# Communication.net
KiCad netlist of a schematic drawn in Altium Designer
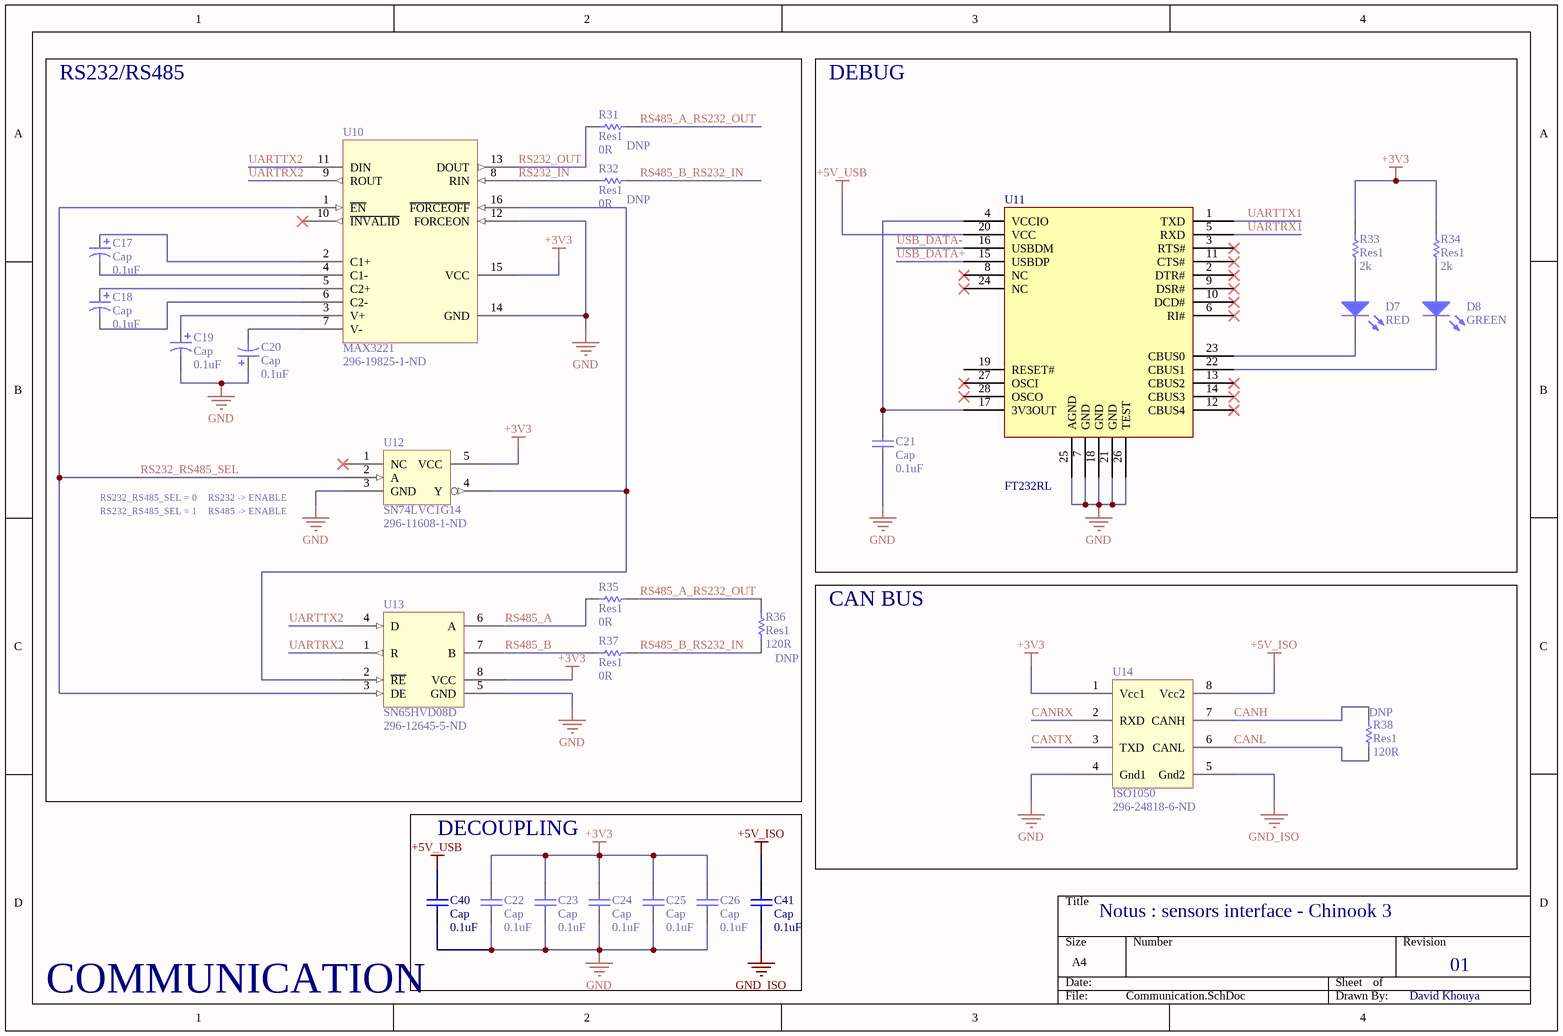
[diagram p0: Communication.SchDoc]

(export (version "E")
  (design (tool "Eeschema 10.0.6"))
  (components
    (comp (ref "C17")
      (value "Cap")
      (footprint "C0805")
      (description "Polarized Capacitor (Surface Mount)")
      (fields (field (name "ALTIUM_VALUE") "0.1uF") (field (name "PUBLISHER") "Altium Limited"))
      (libsource (lib "Miscellaneous Devices") (part "Cap Pol3"))
    )
    (comp (ref "C18")
      (value "Cap")
      (footprint "C0805")
      (description "Polarized Capacitor (Surface Mount)")
      (fields (field (name "ALTIUM_VALUE") "0.1uF") (field (name "PUBLISHER") "Altium Limited"))
      (libsource (lib "Miscellaneous Devices") (part "Cap Pol3"))
    )
    (comp (ref "C19")
      (value "Cap")
      (footprint "C0805")
      (description "Polarized Capacitor (Surface Mount)")
      (fields (field (name "ALTIUM_VALUE") "0.1uF") (field (name "PUBLISHER") "Altium Limited"))
      (libsource (lib "Miscellaneous Devices") (part "Cap Pol3"))
    )
    (comp (ref "C20")
      (value "Cap")
      (footprint "C0805")
      (description "Polarized Capacitor (Surface Mount)")
      (fields (field (name "ALTIUM_VALUE") "0.1uF") (field (name "PUBLISHER") "Altium Limited"))
      (libsource (lib "Miscellaneous Devices") (part "Cap Pol3"))
    )
    (comp (ref "C21")
      (value "Cap")
      (footprint "RESC2012N")
      (description "Capacitor")
      (fields (field (name "ALTIUM_VALUE") "0.1uF") (field (name "PUBLISHER") "Altium Limited"))
      (libsource (lib "Miscellaneous Devices") (part "Cap"))
    )
    (comp (ref "C22")
      (value "Cap")
      (footprint "RESC2012N")
      (description "Capacitor")
      (fields (field (name "ALTIUM_VALUE") "0.1uF") (field (name "PUBLISHER") "Altium Limited"))
      (libsource (lib "Miscellaneous Devices") (part "Cap"))
    )
    (comp (ref "C23")
      (value "Cap")
      (footprint "RESC2012N")
      (description "Capacitor")
      (fields (field (name "ALTIUM_VALUE") "0.1uF") (field (name "PUBLISHER") "Altium Limited"))
      (libsource (lib "Miscellaneous Devices") (part "Cap"))
    )
    (comp (ref "C24")
      (value "Cap")
      (footprint "RESC2012N")
      (description "Capacitor")
      (fields (field (name "ALTIUM_VALUE") "0.1uF") (field (name "PUBLISHER") "Altium Limited"))
      (libsource (lib "Miscellaneous Devices") (part "Cap"))
    )
    (comp (ref "C25")
      (value "Cap")
      (footprint "RESC2012N")
      (description "Capacitor")
      (fields (field (name "ALTIUM_VALUE") "0.1uF") (field (name "PUBLISHER") "Altium Limited"))
      (libsource (lib "Miscellaneous Devices") (part "Cap"))
    )
    (comp (ref "C26")
      (value "Cap")
      (footprint "RESC2012N")
      (description "Capacitor")
      (fields (field (name "ALTIUM_VALUE") "0.1uF") (field (name "PUBLISHER") "Altium Limited"))
      (libsource (lib "Miscellaneous Devices") (part "Cap"))
    )
    (comp (ref "C40")
      (value "Cap")
      (footprint "RESC2012N")
      (description "Capacitor")
      (fields (field (name "ALTIUM_VALUE") "0.1uF") (field (name "PUBLISHER") "Altium Limited"))
      (libsource (lib "Miscellaneous Devices") (part "Cap"))
    )
    (comp (ref "C41")
      (value "Cap")
      (footprint "RESC2012N")
      (description "Capacitor")
      (fields (field (name "ALTIUM_VALUE") "0.1uF") (field (name "PUBLISHER") "Altium Limited"))
      (libsource (lib "Miscellaneous Devices") (part "Cap"))
    )
    (comp (ref "D7")
      (value "RED")
      (footprint "0805_Diode")
      (description "Typical INFRARED GaAs LED")
      (fields (field (name "PUBLISHER") "Altium Limited"))
      (libsource (lib "Miscellaneous Devices") (part "LED0"))
    )
    (comp (ref "D8")
      (value "GREEN")
      (footprint "0805_Diode")
      (description "Typical INFRARED GaAs LED")
      (fields (field (name "PUBLISHER") "Altium Limited"))
      (libsource (lib "Miscellaneous Devices") (part "LED0"))
    )
    (comp (ref "R31")
      (value "Res1")
      (footprint "RESC2012N")
      (description "Resistor")
      (fields
        (field (name "ALTIUM_VALUE") "0R")
        (field (name "DNP") "DNP")
        (field (name "PUBLISHER") "Altium Limited")
      )
      (libsource (lib "Miscellaneous Devices") (part "Res1"))
    )
    (comp (ref "R32")
      (value "Res1")
      (footprint "RESC2012N")
      (description "Resistor")
      (fields
        (field (name "ALTIUM_VALUE") "0R")
        (field (name "DNP") "DNP")
        (field (name "PUBLISHER") "Altium Limited")
      )
      (libsource (lib "Miscellaneous Devices") (part "Res1"))
    )
    (comp (ref "R33")
      (value "Res1")
      (footprint "RESC2012N")
      (description "Resistor")
      (fields (field (name "ALTIUM_VALUE") "2k") (field (name "PUBLISHER") "Altium Limited"))
      (libsource (lib "Miscellaneous Devices") (part "Res1"))
    )
    (comp (ref "R34")
      (value "Res1")
      (footprint "RESC2012N")
      (description "Resistor")
      (fields (field (name "ALTIUM_VALUE") "2k") (field (name "PUBLISHER") "Altium Limited"))
      (libsource (lib "Miscellaneous Devices") (part "Res1"))
    )
    (comp (ref "R35")
      (value "Res1")
      (footprint "RESC2012N")
      (description "Resistor")
      (fields (field (name "ALTIUM_VALUE") "0R") (field (name "PUBLISHER") "Altium Limited"))
      (libsource (lib "Miscellaneous Devices") (part "Res1"))
    )
    (comp (ref "R36")
      (value "Res1")
      (footprint "RESC2012N")
      (description "Resistor")
      (fields
        (field (name "ALTIUM_VALUE") "120R")
        (field (name "DNP") "DNP")
        (field (name "PUBLISHER") "Altium Limited")
      )
      (libsource (lib "Miscellaneous Devices") (part "Res1"))
    )
    (comp (ref "R37")
      (value "Res1")
      (footprint "RESC2012N")
      (description "Resistor")
      (fields (field (name "ALTIUM_VALUE") "0R") (field (name "PUBLISHER") "Altium Limited"))
      (libsource (lib "Miscellaneous Devices") (part "Res1"))
    )
    (comp (ref "R38")
      (value "Res1")
      (footprint "RESC2012N")
      (description "Resistor")
      (fields
        (field (name "ALTIUM_VALUE") "120R")
        (field (name "DNP") "DNP")
        (field (name "PUBLISHER") "Altium Limited")
      )
      (libsource (lib "Miscellaneous Devices") (part "Res1"))
    )
    (comp (ref "U10")
      (value "MAX3221")
      (footprint "SSOP16_M")
      (description "RS232 to TTL")
      (fields (field (name "SUPPLIER PART NUMBER 1") "296-19825-1-ND"))
      (libsource (lib "dkhouya") (part "MAX3221"))
    )
    (comp (ref "U11")
      (value "FT232RL")
      (footprint "ssop-28")
      (description "USB UART IC")
      (libsource (lib "dkhouya") (part "FT232RL"))
    )
    (comp (ref "U12")
      (value "SN74LVC1G14")
      (footprint "SOT23-5AM")
      (description "Inverter Gate")
      (fields (field (name "SUPPLIER PART NUMBER 1") "296-11608-1-ND"))
      (libsource (lib "dkhouya") (part "SN74LVC1G14"))
    )
    (comp (ref "U13")
      (value "SN65HVD08D")
      (footprint "8SOIC-2")
      (description "RS485 to TTL")
      (fields (field (name "SUPPLIER PART NUMBER 1") "296-12645-5-ND"))
      (libsource (lib "dkhouya") (part "SN65HVD08D"))
    )
    (comp (ref "U14")
      (value "ISO1050")
      (footprint "SOP-8")
      (description "ISOLATED CAN TRANSCEIVER")
      (fields (field (name "SUPPLIER PART NUMBER 1") "296-24818-6-ND"))
      (libsource (lib "dkhouya") (part "ISO1050"))
    )
  )
  (nets
    (net (code "1") (name "+3V3") (class "Default")
      (node (ref "C22") (pin "2") (pinfunction "2_2") (pintype "passive"))
      (node (ref "C23") (pin "2") (pinfunction "2_2") (pintype "passive"))
      (node (ref "C24") (pin "2") (pinfunction "2_2") (pintype "passive"))
      (node (ref "C25") (pin "2") (pinfunction "2_2") (pintype "passive"))
      (node (ref "C26") (pin "2") (pinfunction "2_2") (pintype "passive"))
      (node (ref "R33") (pin "1") (pinfunction "1_1") (pintype "passive"))
      (node (ref "R34") (pin "1") (pinfunction "1_1") (pintype "passive"))
      (node (ref "U10") (pin "15") (pinfunction "VCC_15") (pintype "power_in"))
      (node (ref "U12") (pin "5") (pinfunction "VCC_5") (pintype "power_in"))
      (node (ref "U13") (pin "8") (pinfunction "VCC_8") (pintype "power_in"))
      (node (ref "U14") (pin "1") (pinfunction "Vcc1_1") (pintype "power_in"))
    )
    (net (code "2") (name "+5V_ISO") (class "Default")
      (node (ref "C41") (pin "2") (pinfunction "2_2") (pintype "passive"))
      (node (ref "U14") (pin "8") (pinfunction "Vcc2_8") (pintype "passive"))
    )
    (net (code "3") (name "+5V_USB") (class "Default")
      (node (ref "C40") (pin "2") (pinfunction "2_2") (pintype "passive"))
      (node (ref "U11") (pin "20") (pinfunction "VCC_20") (pintype "passive"))
    )
    (net (code "4") (name "/CANH") (class "Default")
      (node (ref "R38") (pin "1") (pinfunction "1_1") (pintype "passive"))
      (node (ref "U14") (pin "7") (pinfunction "CANH_7") (pintype "passive"))
    )
    (net (code "5") (name "/CANL") (class "Default")
      (node (ref "R38") (pin "2") (pinfunction "2_2") (pintype "passive"))
      (node (ref "U14") (pin "6") (pinfunction "CANL_6") (pintype "passive"))
    )
    (net (code "6") (name "/CANRX") (class "Default")
      (node (ref "U14") (pin "2") (pinfunction "RXD_2") (pintype "passive"))
    )
    (net (code "7") (name "/CANTX") (class "Default")
      (node (ref "U14") (pin "3") (pinfunction "TXD_3") (pintype "passive"))
    )
    (net (code "8") (name "/RS232_IN") (class "Default")
      (node (ref "R32") (pin "1") (pinfunction "1_1") (pintype "passive"))
      (node (ref "U10") (pin "8") (pinfunction "RIN_8") (pintype "input"))
    )
    (net (code "9") (name "/RS232_OUT") (class "Default")
      (node (ref "R31") (pin "1") (pinfunction "1_1") (pintype "passive"))
      (node (ref "U10") (pin "13") (pinfunction "DOUT_13") (pintype "output"))
    )
    (net (code "10") (name "/RS232_RS485_SEL") (class "Default")
      (node (ref "U10") (pin "1") (pinfunction "~{EN}_1") (pintype "input"))
      (node (ref "U12") (pin "2") (pinfunction "A_2") (pintype "input"))
      (node (ref "U13") (pin "3") (pinfunction "DE_3") (pintype "input"))
    )
    (net (code "11") (name "/RS485_A") (class "Default")
      (node (ref "R35") (pin "1") (pinfunction "1_1") (pintype "passive"))
      (node (ref "U13") (pin "6") (pinfunction "A_6") (pintype "passive"))
    )
    (net (code "12") (name "/RS485_A_RS232_OUT") (class "Default")
      (node (ref "R31") (pin "2") (pinfunction "2_2") (pintype "passive"))
      (node (ref "R35") (pin "2") (pinfunction "2_2") (pintype "passive"))
      (node (ref "R36") (pin "2") (pinfunction "2_2") (pintype "passive"))
    )
    (net (code "13") (name "/RS485_B") (class "Default")
      (node (ref "R37") (pin "1") (pinfunction "1_1") (pintype "passive"))
      (node (ref "U13") (pin "7") (pinfunction "B_7") (pintype "passive"))
    )
    (net (code "14") (name "/RS485_B_RS232_IN") (class "Default")
      (node (ref "R32") (pin "2") (pinfunction "2_2") (pintype "passive"))
      (node (ref "R36") (pin "1") (pinfunction "1_1") (pintype "passive"))
      (node (ref "R37") (pin "2") (pinfunction "2_2") (pintype "passive"))
    )
    (net (code "15") (name "/UARTRX1") (class "Default")
      (node (ref "U11") (pin "5") (pinfunction "RXD_5") (pintype "passive"))
    )
    (net (code "16") (name "/UARTRX2") (class "Default")
      (node (ref "U10") (pin "9") (pinfunction "ROUT_9") (pintype "output"))
      (node (ref "U13") (pin "1") (pinfunction "R_1") (pintype "output"))
    )
    (net (code "17") (name "/UARTTX1") (class "Default")
      (node (ref "U11") (pin "1") (pinfunction "TXD_1") (pintype "passive"))
    )
    (net (code "18") (name "/UARTTX2") (class "Default")
      (node (ref "U10") (pin "11") (pinfunction "DIN_11") (pintype "passive"))
      (node (ref "U13") (pin "4") (pinfunction "D_4") (pintype "input"))
    )
    (net (code "19") (name "/USB_DATA+") (class "Default")
      (node (ref "U11") (pin "15") (pinfunction "USBDP_15") (pintype "passive"))
    )
    (net (code "20") (name "/USB_DATA-") (class "Default")
      (node (ref "U11") (pin "16") (pinfunction "USBDM_16") (pintype "passive"))
    )
    (net (code "21") (name "GND") (class "Default")
      (node (ref "C19") (pin "2") (pinfunction "2_2") (pintype "passive"))
      (node (ref "C20") (pin "1") (pinfunction "1_1") (pintype "passive"))
      (node (ref "C21") (pin "1") (pinfunction "1_1") (pintype "passive"))
      (node (ref "C22") (pin "1") (pinfunction "1_1") (pintype "passive"))
      (node (ref "C23") (pin "1") (pinfunction "1_1") (pintype "passive"))
      (node (ref "C24") (pin "1") (pinfunction "1_1") (pintype "passive"))
      (node (ref "C25") (pin "1") (pinfunction "1_1") (pintype "passive"))
      (node (ref "C26") (pin "1") (pinfunction "1_1") (pintype "passive"))
      (node (ref "C40") (pin "1") (pinfunction "1_1") (pintype "passive"))
      (node (ref "U10") (pin "12") (pinfunction "FORCEON_12") (pintype "input"))
      (node (ref "U10") (pin "14") (pinfunction "GND_14") (pintype "power_in"))
      (node (ref "U11") (pin "18") (pinfunction "GND_18") (pintype "passive"))
      (node (ref "U11") (pin "21") (pinfunction "GND_21") (pintype "passive"))
      (node (ref "U11") (pin "25") (pinfunction "AGND_25") (pintype "passive"))
      (node (ref "U11") (pin "26") (pinfunction "TEST_26") (pintype "passive"))
      (node (ref "U11") (pin "7") (pinfunction "GND_7") (pintype "passive"))
      (node (ref "U12") (pin "3") (pinfunction "GND_3") (pintype "power_in"))
      (node (ref "U13") (pin "5") (pinfunction "GND_5") (pintype "power_in"))
      (node (ref "U14") (pin "4") (pinfunction "Gnd1_4") (pintype "passive"))
    )
    (net (code "22") (name "GND_ISO") (class "Default")
      (node (ref "C41") (pin "1") (pinfunction "1_1") (pintype "passive"))
      (node (ref "U14") (pin "5") (pinfunction "Gnd2_5") (pintype "passive"))
    )
    (net (code "23") (name "Net-(D7-A)") (class "Default")
      (node (ref "D7") (pin "1") (pinfunction "A_1") (pintype "passive"))
      (node (ref "R33") (pin "2") (pinfunction "2_2") (pintype "passive"))
    )
    (net (code "24") (name "Net-(D7-K)") (class "Default")
      (node (ref "D7") (pin "2") (pinfunction "K_2") (pintype "passive"))
      (node (ref "U11") (pin "23") (pinfunction "CBUS0_23") (pintype "passive"))
    )
    (net (code "25") (name "Net-(D8-A)") (class "Default")
      (node (ref "D8") (pin "1") (pinfunction "A_1") (pintype "passive"))
      (node (ref "R34") (pin "2") (pinfunction "2_2") (pintype "passive"))
    )
    (net (code "26") (name "Net-(D8-K)") (class "Default")
      (node (ref "D8") (pin "2") (pinfunction "K_2") (pintype "passive"))
      (node (ref "U11") (pin "22") (pinfunction "CBUS1_22") (pintype "passive"))
    )
    (net (code "27") (name "Net-(U10-C1+)") (class "Default")
      (node (ref "C17") (pin "1") (pinfunction "1_1") (pintype "passive"))
      (node (ref "U10") (pin "2") (pinfunction "C1+_2") (pintype "passive"))
    )
    (net (code "28") (name "Net-(U10-C1-)") (class "Default")
      (node (ref "C17") (pin "2") (pinfunction "2_2") (pintype "passive"))
      (node (ref "U10") (pin "4") (pinfunction "C1-_4") (pintype "passive"))
    )
    (net (code "29") (name "Net-(U10-C2+)") (class "Default")
      (node (ref "C18") (pin "1") (pinfunction "1_1") (pintype "passive"))
      (node (ref "U10") (pin "5") (pinfunction "C2+_5") (pintype "passive"))
    )
    (net (code "30") (name "Net-(U10-C2-)") (class "Default")
      (node (ref "C18") (pin "2") (pinfunction "2_2") (pintype "passive"))
      (node (ref "U10") (pin "6") (pinfunction "C2-_6") (pintype "passive"))
    )
    (net (code "31") (name "Net-(U10-V+)") (class "Default")
      (node (ref "C19") (pin "1") (pinfunction "1_1") (pintype "passive"))
      (node (ref "U10") (pin "3") (pinfunction "V+_3") (pintype "passive"))
    )
    (net (code "32") (name "Net-(U10-V-)") (class "Default")
      (node (ref "C20") (pin "2") (pinfunction "2_2") (pintype "passive"))
      (node (ref "U10") (pin "7") (pinfunction "V-_7") (pintype "passive"))
    )
    (net (code "33") (name "Net-(U10-~{FORCEOFF})") (class "Default")
      (node (ref "U10") (pin "16") (pinfunction "~{FORCEOFF}_16") (pintype "input"))
      (node (ref "U12") (pin "4") (pinfunction "Y_4") (pintype "output"))
      (node (ref "U13") (pin "2") (pinfunction "~{RE}_2") (pintype "input"))
    )
    (net (code "34") (name "Net-(U11-3V3OUT)") (class "Default")
      (node (ref "C21") (pin "2") (pinfunction "2_2") (pintype "passive"))
      (node (ref "U11") (pin "17") (pinfunction "3V3OUT_17") (pintype "passive"))
      (node (ref "U11") (pin "4") (pinfunction "VCCIO_4") (pintype "passive"))
    )
    (net (code "35") (name "unconnected-(U10-~{INVALID}-Pad10)") (class "Default")
      (node (ref "U10") (pin "10") (pinfunction "~{INVALID}_10") (pintype "output+no_connect"))
    )
    (net (code "36") (name "unconnected-(U11-CBUS2-Pad13)") (class "Default")
      (node (ref "U11") (pin "13") (pinfunction "CBUS2_13") (pintype "passive+no_connect"))
    )
    (net (code "37") (name "unconnected-(U11-CBUS3-Pad14)") (class "Default")
      (node (ref "U11") (pin "14") (pinfunction "CBUS3_14") (pintype "passive+no_connect"))
    )
    (net (code "38") (name "unconnected-(U11-CBUS4-Pad12)") (class "Default")
      (node (ref "U11") (pin "12") (pinfunction "CBUS4_12") (pintype "passive+no_connect"))
    )
    (net (code "39") (name "unconnected-(U11-CTS#-Pad11)") (class "Default")
      (node (ref "U11") (pin "11") (pinfunction "CTS#_11") (pintype "passive+no_connect"))
    )
    (net (code "40") (name "unconnected-(U11-DCD#-Pad10)") (class "Default")
      (node (ref "U11") (pin "10") (pinfunction "DCD#_10") (pintype "passive+no_connect"))
    )
    (net (code "41") (name "unconnected-(U11-DSR#-Pad9)") (class "Default")
      (node (ref "U11") (pin "9") (pinfunction "DSR#_9") (pintype "passive+no_connect"))
    )
    (net (code "42") (name "unconnected-(U11-DTR#-Pad2)") (class "Default")
      (node (ref "U11") (pin "2") (pinfunction "DTR#_2") (pintype "passive+no_connect"))
    )
    (net (code "43") (name "unconnected-(U11-NC-Pad8)") (class "Default")
      (node (ref "U11") (pin "8") (pinfunction "NC_8") (pintype "passive+no_connect"))
    )
    (net (code "44") (name "unconnected-(U11-NC-Pad24)") (class "Default")
      (node (ref "U11") (pin "24") (pinfunction "NC_24") (pintype "passive+no_connect"))
    )
    (net (code "45") (name "unconnected-(U11-OSCI-Pad27)") (class "Default")
      (node (ref "U11") (pin "27") (pinfunction "OSCI_27") (pintype "passive+no_connect"))
    )
    (net (code "46") (name "unconnected-(U11-OSCO-Pad28)") (class "Default")
      (node (ref "U11") (pin "28") (pinfunction "OSCO_28") (pintype "passive+no_connect"))
    )
    (net (code "47") (name "unconnected-(U11-RESET#-Pad19)") (class "Default")
      (node (ref "U11") (pin "19") (pinfunction "RESET#_19") (pintype "passive"))
    )
    (net (code "48") (name "unconnected-(U11-RI#-Pad6)") (class "Default")
      (node (ref "U11") (pin "6") (pinfunction "RI#_6") (pintype "passive+no_connect"))
    )
    (net (code "49") (name "unconnected-(U11-RTS#-Pad3)") (class "Default")
      (node (ref "U11") (pin "3") (pinfunction "RTS#_3") (pintype "passive+no_connect"))
    )
    (net (code "50") (name "unconnected-(U12-NC-Pad1)") (class "Default")
      (node (ref "U12") (pin "1") (pinfunction "NC_1") (pintype "passive+no_connect"))
    )
  )
)
